# Schematic-1.net
KiCad netlist of a schematic drawn in EAGLE
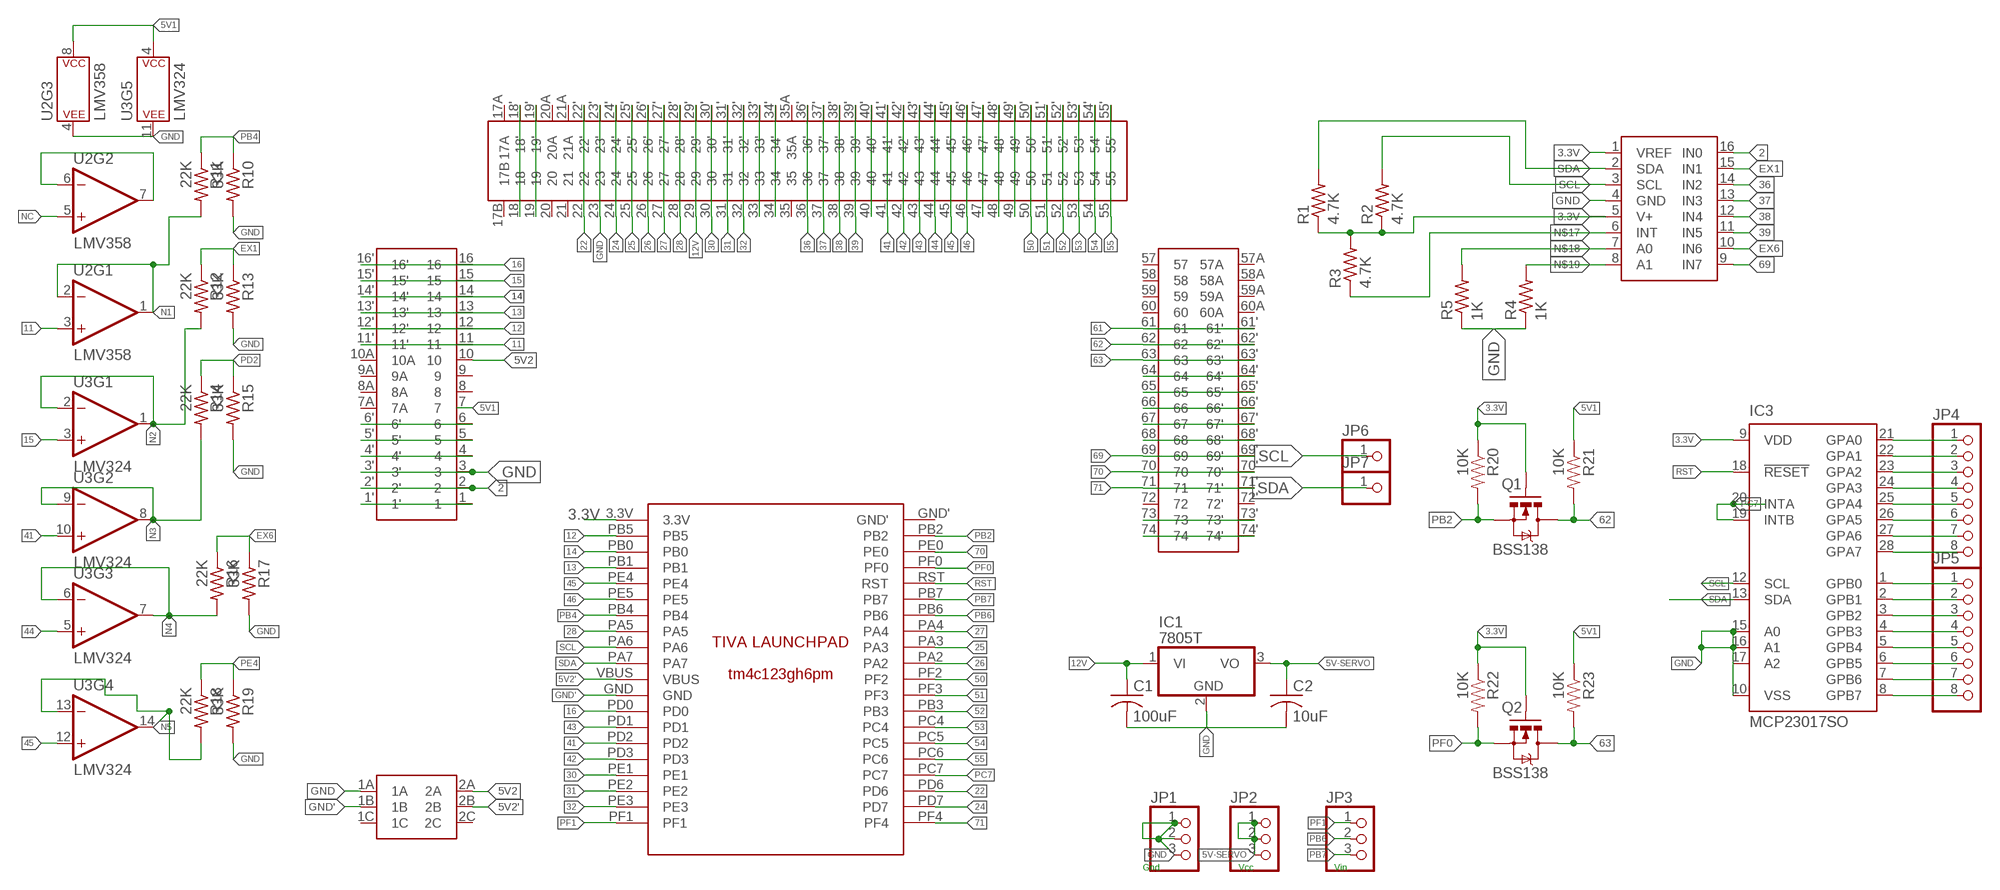
[diagram p0: schematic, sheet 1]

(export (version "E")
  (design (tool "Eeschema 10.0.6"))
  (components
    (comp (ref "C1")
      (value "100uF")
      (footprint "eagle-import:C025-030X050")
      (libsource (lib "eagle-import") (part "C-US025-030X050"))
    )
    (comp (ref "C2")
      (value "10uF")
      (footprint "eagle-import:C025-030X050")
      (libsource (lib "eagle-import") (part "C-US025-030X050"))
    )
    (comp (ref "IC1")
      (value "7805T")
      (footprint "eagle-import:TO220H")
      (libsource (lib "eagle-import") (part "78T05"))
    )
    (comp (ref "IC3")
      (value "MCP23017SO")
      (footprint "eagle-import:SO28W")
      (libsource (lib "eagle-import") (part "MCP23017SO"))
    )
    (comp (ref "JP1")
      (value "PINHD-1X3")
      (footprint "eagle-import:1X03")
      (libsource (lib "eagle-import") (part "PINHD-1X3"))
    )
    (comp (ref "JP2")
      (value "PINHD-1X3")
      (footprint "eagle-import:1X03")
      (libsource (lib "eagle-import") (part "PINHD-1X3"))
    )
    (comp (ref "JP3")
      (value "PINHD-1X3")
      (footprint "eagle-import:1X03")
      (libsource (lib "eagle-import") (part "PINHD-1X3"))
    )
    (comp (ref "JP4")
      (value "PINHD-1X8BIG")
      (footprint "eagle-import:1X08-BIG")
      (libsource (lib "eagle-import") (part "PINHD-1X8BIG"))
    )
    (comp (ref "JP5")
      (value "PINHD-1X8BIG")
      (footprint "eagle-import:1X08-BIG")
      (libsource (lib "eagle-import") (part "PINHD-1X8BIG"))
    )
    (comp (ref "JP6")
      (value "PINHD-1X1")
      (footprint "eagle-import:1X01")
      (libsource (lib "eagle-import") (part "PINHD-1X1"))
    )
    (comp (ref "JP7")
      (value "PINHD-1X1")
      (footprint "eagle-import:1X01")
      (libsource (lib "eagle-import") (part "PINHD-1X1"))
    )
    (comp (ref "Q1")
      (value "BSS138")
      (footprint "eagle-import:SOT23-3")
      (libsource (lib "eagle-import") (part "MOSFET-NCHANNELSMD"))
    )
    (comp (ref "Q2")
      (value "BSS138")
      (footprint "eagle-import:SOT23-3")
      (libsource (lib "eagle-import") (part "MOSFET-NCHANNELSMD"))
    )
    (comp (ref "R1")
      (value "4.7K")
      (footprint "eagle-import:M1206")
      (libsource (lib "eagle-import") (part "rcl_R-US_M1206"))
    )
    (comp (ref "R2")
      (value "4.7K")
      (footprint "eagle-import:M1206")
      (libsource (lib "eagle-import") (part "rcl_R-US_M1206"))
    )
    (comp (ref "R3")
      (value "4.7K")
      (footprint "eagle-import:M1206")
      (libsource (lib "eagle-import") (part "rcl_R-US_M1206"))
    )
    (comp (ref "R4")
      (value "1K")
      (footprint "eagle-import:M1206")
      (libsource (lib "eagle-import") (part "rcl_R-US_M1206"))
    )
    (comp (ref "R5")
      (value "1K")
      (footprint "eagle-import:M1206")
      (libsource (lib "eagle-import") (part "rcl_R-US_M1206"))
    )
    (comp (ref "R10")
      (value "33K")
      (footprint "eagle-import:M1206")
      (libsource (lib "eagle-import") (part "R-US_M1206"))
    )
    (comp (ref "R11")
      (value "22K")
      (footprint "eagle-import:M1206")
      (libsource (lib "eagle-import") (part "R-US_M1206"))
    )
    (comp (ref "R12")
      (value "22K")
      (footprint "eagle-import:M1206")
      (libsource (lib "eagle-import") (part "R-US_M1206"))
    )
    (comp (ref "R13")
      (value "33K")
      (footprint "eagle-import:M1206")
      (libsource (lib "eagle-import") (part "R-US_M1206"))
    )
    (comp (ref "R14")
      (value "22K")
      (footprint "eagle-import:M1206")
      (libsource (lib "eagle-import") (part "R-US_M1206"))
    )
    (comp (ref "R15")
      (value "33K")
      (footprint "eagle-import:M1206")
      (libsource (lib "eagle-import") (part "R-US_M1206"))
    )
    (comp (ref "R16")
      (value "22K")
      (footprint "eagle-import:M1206")
      (libsource (lib "eagle-import") (part "R-US_M1206"))
    )
    (comp (ref "R17")
      (value "33K")
      (footprint "eagle-import:M1206")
      (libsource (lib "eagle-import") (part "R-US_M1206"))
    )
    (comp (ref "R18")
      (value "22K")
      (footprint "eagle-import:M1206")
      (libsource (lib "eagle-import") (part "R-US_M1206"))
    )
    (comp (ref "R19")
      (value "33K")
      (footprint "eagle-import:M1206")
      (libsource (lib "eagle-import") (part "R-US_M1206"))
    )
    (comp (ref "R20")
      (value "10K")
      (footprint "eagle-import:1206")
      (libsource (lib "eagle-import") (part "RESISTOR1206"))
    )
    (comp (ref "R21")
      (value "10K")
      (footprint "eagle-import:1206")
      (libsource (lib "eagle-import") (part "RESISTOR1206"))
    )
    (comp (ref "R22")
      (value "10K")
      (footprint "eagle-import:1206")
      (libsource (lib "eagle-import") (part "RESISTOR1206"))
    )
    (comp (ref "R23")
      (value "10K")
      (footprint "eagle-import:1206")
      (libsource (lib "eagle-import") (part "RESISTOR1206"))
    )
    (comp (ref "U$1")
      (value "DAUGHTERBOARDDAUGHTERBOARD")
      (footprint "eagle-import:DAUGHTERBOARD")
      (libsource (lib "eagle-import") (part "DAUGHTERBOARDDAUGHTERBOARD"))
    )
    (comp (ref "U$2")
      (value "TIVA_LAUNCHPADTIVA_LAUNCHPAD")
      (footprint "eagle-import:TIVA_LAUNCHPAD")
      (libsource (lib "eagle-import") (part "TIVA_LAUNCHPADTIVA_LAUNCHPAD"))
    )
    (comp (ref "U$3")
      (value "SELF-LOCKING_SWITCHSELF-LOCKING_SWITCH")
      (footprint "eagle-import:SELF-LOCKING_SWITCH")
      (libsource (lib "eagle-import") (part "SELF-LOCKING_SWITCHSELF-LOCKING_SWITCH"))
    )
    (comp (ref "U$4")
      (value "ADC128D818")
      (footprint "eagle-import:ADC12_SD")
      (libsource (lib "eagle-import") (part "ADC128D818"))
    )
    (comp (ref "U2")
      (value "LMV358")
      (footprint "eagle-import:SO08")
      (libsource (lib "eagle-import") (part "LMV358SOIC"))
    )
    (comp (ref "U3")
      (value "LMV324")
      (footprint "eagle-import:SO14")
      (libsource (lib "eagle-import") (part "LMV324"))
    )
  )
  (nets
    (net (code "1") (name "2") (class "Default")
      (node (ref "U$1") (pin "2") (pinfunction "2_2") (pintype "output"))
      (node (ref "U$1") (pin "2'") (pinfunction "2'_2'") (pintype "output"))
      (node (ref "U$4") (pin "16") (pinfunction "IN0_16") (pintype "bidirectional"))
    )
    (net (code "2") (name "3.3V") (class "Default")
      (node (ref "IC3") (pin "9") (pinfunction "VDD_9") (pintype "power_in"))
      (node (ref "Q1") (pin "1") (pinfunction "G_1") (pintype "passive"))
      (node (ref "Q2") (pin "1") (pinfunction "G_1") (pintype "passive"))
      (node (ref "R1") (pin "1") (pinfunction "1_1") (pintype "passive"))
      (node (ref "R2") (pin "1") (pinfunction "1_1") (pintype "passive"))
      (node (ref "R20") (pin "1") (pinfunction "1_1") (pintype "passive"))
      (node (ref "R22") (pin "1") (pinfunction "1_1") (pintype "passive"))
      (node (ref "R3") (pin "2") (pinfunction "2_2") (pintype "passive"))
      (node (ref "U$2") (pin "3.3V") (pinfunction "3.3V_3.3V") (pintype "bidirectional"))
      (node (ref "U$4") (pin "1") (pinfunction "VREF_1") (pintype "bidirectional"))
      (node (ref "U$4") (pin "5") (pinfunction "V+_5") (pintype "bidirectional"))
    )
    (net (code "3") (name "5V-SERVO") (class "Default")
      (node (ref "C2") (pin "1") (pinfunction "1_1") (pintype "passive"))
      (node (ref "IC1") (pin "3") (pinfunction "VO_3") (pintype "passive"))
      (node (ref "JP2") (pin "1") (pinfunction "1_1") (pintype "passive"))
      (node (ref "JP2") (pin "2") (pinfunction "2_2") (pintype "passive"))
      (node (ref "JP2") (pin "3") (pinfunction "3_3") (pintype "passive"))
    )
    (net (code "4") (name "5V1") (class "Default")
      (node (ref "R21") (pin "1") (pinfunction "1_1") (pintype "passive"))
      (node (ref "R23") (pin "1") (pinfunction "1_1") (pintype "passive"))
      (node (ref "U$1") (pin "7") (pinfunction "7_7") (pintype "output"))
      (node (ref "U2") (pin "8") (pinfunction "P$V+_8") (pintype "bidirectional"))
      (node (ref "U3") (pin "4") (pinfunction "P$V+_4") (pintype "bidirectional"))
    )
    (net (code "5") (name "5V2") (class "Default")
      (node (ref "U$1") (pin "10") (pinfunction "10_10") (pintype "output"))
      (node (ref "U$3") (pin "2A") (pinfunction "2A_2A") (pintype "bidirectional"))
    )
    (net (code "6") (name "5V2'") (class "Default")
      (node (ref "U$2") (pin "VBUS") (pinfunction "VBUS_VBUS") (pintype "bidirectional"))
      (node (ref "U$3") (pin "2B") (pinfunction "2B_2B") (pintype "bidirectional"))
    )
    (net (code "7") (name "11") (class "Default")
      (node (ref "U$1") (pin "11") (pinfunction "11_11") (pintype "output"))
      (node (ref "U$1") (pin "11'") (pinfunction "11'_11'") (pintype "output"))
      (node (ref "U2") (pin "3") (pinfunction "+IN_3") (pintype "input"))
    )
    (net (code "8") (name "12") (class "Default")
      (node (ref "U$1") (pin "12") (pinfunction "12_12") (pintype "output"))
      (node (ref "U$1") (pin "12'") (pinfunction "12'_12'") (pintype "output"))
      (node (ref "U$2") (pin "PB5") (pinfunction "PB5_PB5") (pintype "bidirectional"))
    )
    (net (code "9") (name "12V") (class "Default")
      (node (ref "C1") (pin "1") (pinfunction "1_1") (pintype "passive"))
      (node (ref "IC1") (pin "1") (pinfunction "VI_1") (pintype "input"))
      (node (ref "U$1") (pin "29") (pinfunction "29_29") (pintype "output"))
      (node (ref "U$1") (pin "29'") (pinfunction "29'_29'") (pintype "output"))
    )
    (net (code "10") (name "13") (class "Default")
      (node (ref "U$1") (pin "13") (pinfunction "13_13") (pintype "output"))
      (node (ref "U$1") (pin "13'") (pinfunction "13'_13'") (pintype "output"))
      (node (ref "U$2") (pin "PB1") (pinfunction "PB1_PB1") (pintype "bidirectional"))
    )
    (net (code "11") (name "14") (class "Default")
      (node (ref "U$1") (pin "14") (pinfunction "14_14") (pintype "output"))
      (node (ref "U$1") (pin "14'") (pinfunction "14'_14'") (pintype "output"))
      (node (ref "U$2") (pin "PB0") (pinfunction "PB0_PB0") (pintype "bidirectional"))
    )
    (net (code "12") (name "15") (class "Default")
      (node (ref "U$1") (pin "15") (pinfunction "15_15") (pintype "output"))
      (node (ref "U$1") (pin "15'") (pinfunction "15'_15'") (pintype "output"))
      (node (ref "U3") (pin "3") (pinfunction "+IN_3") (pintype "input"))
    )
    (net (code "13") (name "16") (class "Default")
      (node (ref "U$1") (pin "16") (pinfunction "16_16") (pintype "output"))
      (node (ref "U$1") (pin "16'") (pinfunction "16'_16'") (pintype "output"))
      (node (ref "U$2") (pin "PD0") (pinfunction "PD0_PD0") (pintype "bidirectional"))
    )
    (net (code "14") (name "22") (class "Default")
      (node (ref "U$1") (pin "22") (pinfunction "22_22") (pintype "output"))
      (node (ref "U$1") (pin "22'") (pinfunction "22'_22'") (pintype "output"))
      (node (ref "U$2") (pin "PD6") (pinfunction "PD6_PD6") (pintype "bidirectional"))
    )
    (net (code "15") (name "24") (class "Default")
      (node (ref "U$1") (pin "24") (pinfunction "24_24") (pintype "output"))
      (node (ref "U$1") (pin "24'") (pinfunction "24'_24'") (pintype "output"))
      (node (ref "U$2") (pin "PD7") (pinfunction "PD7_PD7") (pintype "bidirectional"))
    )
    (net (code "16") (name "25") (class "Default")
      (node (ref "U$1") (pin "25") (pinfunction "25_25") (pintype "output"))
      (node (ref "U$1") (pin "25'") (pinfunction "25'_25'") (pintype "output"))
      (node (ref "U$2") (pin "PA3") (pinfunction "PA3_PA3") (pintype "bidirectional"))
    )
    (net (code "17") (name "26") (class "Default")
      (node (ref "U$1") (pin "26") (pinfunction "26_26") (pintype "output"))
      (node (ref "U$1") (pin "26'") (pinfunction "26'_26'") (pintype "output"))
      (node (ref "U$2") (pin "PA2") (pinfunction "PA2_PA2") (pintype "bidirectional"))
    )
    (net (code "18") (name "27") (class "Default")
      (node (ref "U$1") (pin "27") (pinfunction "27_27") (pintype "output"))
      (node (ref "U$1") (pin "27'") (pinfunction "27'_27'") (pintype "output"))
      (node (ref "U$2") (pin "PA4") (pinfunction "PA4_PA4") (pintype "bidirectional"))
    )
    (net (code "19") (name "28") (class "Default")
      (node (ref "U$1") (pin "28") (pinfunction "28_28") (pintype "output"))
      (node (ref "U$1") (pin "28'") (pinfunction "28'_28'") (pintype "output"))
      (node (ref "U$2") (pin "PA5") (pinfunction "PA5_PA5") (pintype "bidirectional"))
    )
    (net (code "20") (name "30") (class "Default")
      (node (ref "U$1") (pin "30") (pinfunction "30_30") (pintype "output"))
      (node (ref "U$1") (pin "30'") (pinfunction "30'_30'") (pintype "output"))
      (node (ref "U$2") (pin "PE1") (pinfunction "PE1_PE1") (pintype "bidirectional"))
    )
    (net (code "21") (name "31") (class "Default")
      (node (ref "U$1") (pin "31") (pinfunction "31_31") (pintype "output"))
      (node (ref "U$1") (pin "31'") (pinfunction "31'_31'") (pintype "output"))
      (node (ref "U$2") (pin "PE2") (pinfunction "PE2_PE2") (pintype "bidirectional"))
    )
    (net (code "22") (name "32") (class "Default")
      (node (ref "U$1") (pin "32") (pinfunction "32_32") (pintype "output"))
      (node (ref "U$1") (pin "32'") (pinfunction "32'_32'") (pintype "output"))
      (node (ref "U$2") (pin "PE3") (pinfunction "PE3_PE3") (pintype "bidirectional"))
    )
    (net (code "23") (name "36") (class "Default")
      (node (ref "U$1") (pin "36") (pinfunction "36_36") (pintype "output"))
      (node (ref "U$1") (pin "36'") (pinfunction "36'_36'") (pintype "output"))
      (node (ref "U$4") (pin "14") (pinfunction "IN2_14") (pintype "bidirectional"))
    )
    (net (code "24") (name "37") (class "Default")
      (node (ref "U$1") (pin "37") (pinfunction "37_37") (pintype "output"))
      (node (ref "U$1") (pin "37'") (pinfunction "37'_37'") (pintype "output"))
      (node (ref "U$4") (pin "13") (pinfunction "IN3_13") (pintype "bidirectional"))
    )
    (net (code "25") (name "38") (class "Default")
      (node (ref "U$1") (pin "38") (pinfunction "38_38") (pintype "output"))
      (node (ref "U$1") (pin "38'") (pinfunction "38'_38'") (pintype "output"))
      (node (ref "U$4") (pin "12") (pinfunction "IN4_12") (pintype "bidirectional"))
    )
    (net (code "26") (name "39") (class "Default")
      (node (ref "U$1") (pin "39") (pinfunction "39_39") (pintype "output"))
      (node (ref "U$1") (pin "39'") (pinfunction "39'_39'") (pintype "output"))
      (node (ref "U$4") (pin "11") (pinfunction "IN5_11") (pintype "bidirectional"))
    )
    (net (code "27") (name "41") (class "Default")
      (node (ref "U$1") (pin "41") (pinfunction "41_41") (pintype "output"))
      (node (ref "U$1") (pin "41'") (pinfunction "41'_41'") (pintype "output"))
      (node (ref "U$2") (pin "PD2") (pinfunction "PD2_PD2") (pintype "bidirectional"))
      (node (ref "U3") (pin "10") (pinfunction "+IN_10") (pintype "input"))
    )
    (net (code "28") (name "42") (class "Default")
      (node (ref "U$1") (pin "42") (pinfunction "42_42") (pintype "output"))
      (node (ref "U$1") (pin "42'") (pinfunction "42'_42'") (pintype "output"))
      (node (ref "U$2") (pin "PD3") (pinfunction "PD3_PD3") (pintype "bidirectional"))
    )
    (net (code "29") (name "43") (class "Default")
      (node (ref "U$1") (pin "43") (pinfunction "43_43") (pintype "output"))
      (node (ref "U$1") (pin "43'") (pinfunction "43'_43'") (pintype "output"))
      (node (ref "U$2") (pin "PD1") (pinfunction "PD1_PD1") (pintype "bidirectional"))
    )
    (net (code "30") (name "44") (class "Default")
      (node (ref "U$1") (pin "44") (pinfunction "44_44") (pintype "output"))
      (node (ref "U$1") (pin "44'") (pinfunction "44'_44'") (pintype "output"))
      (node (ref "U3") (pin "5") (pinfunction "+IN_5") (pintype "input"))
    )
    (net (code "31") (name "45") (class "Default")
      (node (ref "U$1") (pin "45") (pinfunction "45_45") (pintype "output"))
      (node (ref "U$1") (pin "45'") (pinfunction "45'_45'") (pintype "output"))
      (node (ref "U$2") (pin "PE4") (pinfunction "PE4_PE4") (pintype "bidirectional"))
      (node (ref "U3") (pin "12") (pinfunction "+IN_12") (pintype "input"))
    )
    (net (code "32") (name "46") (class "Default")
      (node (ref "U$1") (pin "46") (pinfunction "46_46") (pintype "output"))
      (node (ref "U$1") (pin "46'") (pinfunction "46'_46'") (pintype "output"))
      (node (ref "U$2") (pin "PE5") (pinfunction "PE5_PE5") (pintype "bidirectional"))
    )
    (net (code "33") (name "50") (class "Default")
      (node (ref "U$1") (pin "50") (pinfunction "50_50") (pintype "output"))
      (node (ref "U$1") (pin "50'") (pinfunction "50'_50'") (pintype "output"))
      (node (ref "U$2") (pin "PF2") (pinfunction "PF2_PF2") (pintype "bidirectional"))
    )
    (net (code "34") (name "51") (class "Default")
      (node (ref "U$1") (pin "51") (pinfunction "51_51") (pintype "output"))
      (node (ref "U$1") (pin "51'") (pinfunction "51'_51'") (pintype "output"))
      (node (ref "U$2") (pin "PF3") (pinfunction "PF3_PF3") (pintype "bidirectional"))
    )
    (net (code "35") (name "52") (class "Default")
      (node (ref "U$1") (pin "52") (pinfunction "52_52") (pintype "output"))
      (node (ref "U$1") (pin "52'") (pinfunction "52'_52'") (pintype "output"))
      (node (ref "U$2") (pin "PB3") (pinfunction "PB3_PB3") (pintype "bidirectional"))
    )
    (net (code "36") (name "53") (class "Default")
      (node (ref "U$1") (pin "53") (pinfunction "53_53") (pintype "output"))
      (node (ref "U$1") (pin "53'") (pinfunction "53'_53'") (pintype "output"))
      (node (ref "U$2") (pin "PC4") (pinfunction "PC4_PC4") (pintype "bidirectional"))
    )
    (net (code "37") (name "54") (class "Default")
      (node (ref "U$1") (pin "54") (pinfunction "54_54") (pintype "output"))
      (node (ref "U$1") (pin "54'") (pinfunction "54'_54'") (pintype "output"))
      (node (ref "U$2") (pin "PC5") (pinfunction "PC5_PC5") (pintype "bidirectional"))
    )
    (net (code "38") (name "55") (class "Default")
      (node (ref "U$1") (pin "55") (pinfunction "55_55") (pintype "output"))
      (node (ref "U$1") (pin "55'") (pinfunction "55'_55'") (pintype "output"))
      (node (ref "U$2") (pin "PC6") (pinfunction "PC6_PC6") (pintype "bidirectional"))
    )
    (net (code "39") (name "61") (class "Default")
      (node (ref "U$1") (pin "61") (pinfunction "61_61") (pintype "output"))
      (node (ref "U$1") (pin "61'") (pinfunction "61'_61'") (pintype "output"))
    )
    (net (code "40") (name "62") (class "Default")
      (node (ref "Q1") (pin "3") (pinfunction "D_3") (pintype "passive"))
      (node (ref "R21") (pin "2") (pinfunction "2_2") (pintype "passive"))
      (node (ref "U$1") (pin "62") (pinfunction "62_62") (pintype "output"))
      (node (ref "U$1") (pin "62'") (pinfunction "62'_62'") (pintype "output"))
    )
    (net (code "41") (name "63") (class "Default")
      (node (ref "Q2") (pin "3") (pinfunction "D_3") (pintype "passive"))
      (node (ref "R23") (pin "2") (pinfunction "2_2") (pintype "passive"))
      (node (ref "U$1") (pin "63") (pinfunction "63_63") (pintype "output"))
      (node (ref "U$1") (pin "63'") (pinfunction "63'_63'") (pintype "output"))
    )
    (net (code "42") (name "69") (class "Default")
      (node (ref "U$1") (pin "69") (pinfunction "69_69") (pintype "output"))
      (node (ref "U$1") (pin "69'") (pinfunction "69'_69'") (pintype "output"))
      (node (ref "U$4") (pin "9") (pinfunction "IN7_9") (pintype "bidirectional"))
    )
    (net (code "43") (name "70") (class "Default")
      (node (ref "U$1") (pin "70") (pinfunction "70_70") (pintype "output"))
      (node (ref "U$1") (pin "70'") (pinfunction "70'_70'") (pintype "output"))
      (node (ref "U$2") (pin "PE0") (pinfunction "PE0_PE0") (pintype "bidirectional"))
    )
    (net (code "44") (name "71") (class "Default")
      (node (ref "U$1") (pin "71") (pinfunction "71_71") (pintype "output"))
      (node (ref "U$1") (pin "71'") (pinfunction "71'_71'") (pintype "output"))
      (node (ref "U$2") (pin "PF4") (pinfunction "PF4_PF4") (pintype "bidirectional"))
    )
    (net (code "45") (name "EX1") (class "Default")
      (node (ref "R12") (pin "1") (pinfunction "1_1") (pintype "passive"))
      (node (ref "R13") (pin "1") (pinfunction "1_1") (pintype "passive"))
      (node (ref "U$4") (pin "15") (pinfunction "IN1_15") (pintype "bidirectional"))
    )
    (net (code "46") (name "EX6") (class "Default")
      (node (ref "R16") (pin "1") (pinfunction "1_1") (pintype "passive"))
      (node (ref "R17") (pin "1") (pinfunction "1_1") (pintype "passive"))
      (node (ref "U$4") (pin "10") (pinfunction "IN6_10") (pintype "bidirectional"))
    )
    (net (code "47") (name "GND") (class "Default")
      (node (ref "C1") (pin "2") (pinfunction "2_2") (pintype "passive"))
      (node (ref "C2") (pin "2") (pinfunction "2_2") (pintype "passive"))
      (node (ref "IC1") (pin "2") (pinfunction "GND_2") (pintype "passive"))
      (node (ref "IC3") (pin "10") (pinfunction "VSS_10") (pintype "power_in"))
      (node (ref "IC3") (pin "15") (pinfunction "A0_15") (pintype "input"))
      (node (ref "IC3") (pin "16") (pinfunction "A1_16") (pintype "input"))
      (node (ref "IC3") (pin "17") (pinfunction "A2_17") (pintype "input"))
      (node (ref "JP1") (pin "1") (pinfunction "1_1") (pintype "passive"))
      (node (ref "JP1") (pin "2") (pinfunction "2_2") (pintype "passive"))
      (node (ref "JP1") (pin "3") (pinfunction "3_3") (pintype "passive"))
      (node (ref "R10") (pin "2") (pinfunction "2_2") (pintype "passive"))
      (node (ref "R13") (pin "2") (pinfunction "2_2") (pintype "passive"))
      (node (ref "R15") (pin "2") (pinfunction "2_2") (pintype "passive"))
      (node (ref "R17") (pin "2") (pinfunction "2_2") (pintype "passive"))
      (node (ref "R19") (pin "2") (pinfunction "2_2") (pintype "passive"))
      (node (ref "R4") (pin "1") (pinfunction "1_1") (pintype "passive"))
      (node (ref "R5") (pin "1") (pinfunction "1_1") (pintype "passive"))
      (node (ref "U$1") (pin "23") (pinfunction "23_23") (pintype "output"))
      (node (ref "U$1") (pin "23'") (pinfunction "23'_23'") (pintype "output"))
      (node (ref "U$1") (pin "3") (pinfunction "3_3") (pintype "output"))
      (node (ref "U$1") (pin "3'") (pinfunction "3'_3'") (pintype "output"))
      (node (ref "U$3") (pin "1A") (pinfunction "1A_1A") (pintype "bidirectional"))
      (node (ref "U$4") (pin "4") (pinfunction "GND_4") (pintype "bidirectional"))
      (node (ref "U2") (pin "4") (pinfunction "P$V-_4") (pintype "bidirectional"))
      (node (ref "U3") (pin "11") (pinfunction "P$V-_11") (pintype "bidirectional"))
    )
    (net (code "48") (name "GND'") (class "Default")
      (node (ref "U$2") (pin "GND") (pinfunction "GND_GND") (pintype "bidirectional"))
      (node (ref "U$3") (pin "1B") (pinfunction "1B_1B") (pintype "bidirectional"))
    )
    (net (code "49") (name "N$17") (class "Default")
      (node (ref "R3") (pin "1") (pinfunction "1_1") (pintype "passive"))
      (node (ref "U$4") (pin "6") (pinfunction "INT_6") (pintype "bidirectional"))
    )
    (net (code "50") (name "N$18") (class "Default")
      (node (ref "R5") (pin "2") (pinfunction "2_2") (pintype "passive"))
      (node (ref "U$4") (pin "7") (pinfunction "A0_7") (pintype "bidirectional"))
    )
    (net (code "51") (name "N$19") (class "Default")
      (node (ref "R4") (pin "2") (pinfunction "2_2") (pintype "passive"))
      (node (ref "U$4") (pin "8") (pinfunction "A1_8") (pintype "bidirectional"))
    )
    (net (code "52") (name "N1") (class "Default")
      (node (ref "R11") (pin "2") (pinfunction "2_2") (pintype "passive"))
      (node (ref "U2") (pin "1") (pinfunction "OUT_1") (pintype "output"))
      (node (ref "U2") (pin "2") (pinfunction "-IN_2") (pintype "input"))
    )
    (net (code "53") (name "N2") (class "Default")
      (node (ref "R12") (pin "2") (pinfunction "2_2") (pintype "passive"))
      (node (ref "U3") (pin "1") (pinfunction "OUT_1") (pintype "output"))
      (node (ref "U3") (pin "2") (pinfunction "-IN_2") (pintype "input"))
    )
    (net (code "54") (name "N3") (class "Default")
      (node (ref "R14") (pin "2") (pinfunction "2_2") (pintype "passive"))
      (node (ref "U3") (pin "8") (pinfunction "OUT_8") (pintype "output"))
      (node (ref "U3") (pin "9") (pinfunction "-IN_9") (pintype "input"))
    )
    (net (code "55") (name "N4") (class "Default")
      (node (ref "R16") (pin "2") (pinfunction "2_2") (pintype "passive"))
      (node (ref "U3") (pin "6") (pinfunction "-IN_6") (pintype "input"))
      (node (ref "U3") (pin "7") (pinfunction "OUT_7") (pintype "output"))
    )
    (net (code "56") (name "N5") (class "Default")
      (node (ref "R18") (pin "2") (pinfunction "2_2") (pintype "passive"))
      (node (ref "U3") (pin "13") (pinfunction "-IN_13") (pintype "input"))
      (node (ref "U3") (pin "14") (pinfunction "OUT_14") (pintype "output"))
    )
    (net (code "57") (name "NC") (class "Default")
      (node (ref "U2") (pin "5") (pinfunction "+IN_5") (pintype "input"))
    )
    (net (code "58") (name "Net-(IC3-GPA0)") (class "Default")
      (node (ref "IC3") (pin "21") (pinfunction "GPA0_21") (pintype "bidirectional"))
      (node (ref "JP4") (pin "1") (pinfunction "1_1") (pintype "passive"))
    )
    (net (code "59") (name "Net-(IC3-GPA1)") (class "Default")
      (node (ref "IC3") (pin "22") (pinfunction "GPA1_22") (pintype "bidirectional"))
      (node (ref "JP4") (pin "2") (pinfunction "2_2") (pintype "passive"))
    )
    (net (code "60") (name "Net-(IC3-GPA2)") (class "Default")
      (node (ref "IC3") (pin "23") (pinfunction "GPA2_23") (pintype "bidirectional"))
      (node (ref "JP4") (pin "3") (pinfunction "3_3") (pintype "passive"))
    )
    (net (code "61") (name "Net-(IC3-GPA3)") (class "Default")
      (node (ref "IC3") (pin "24") (pinfunction "GPA3_24") (pintype "bidirectional"))
      (node (ref "JP4") (pin "4") (pinfunction "4_4") (pintype "passive"))
    )
    (net (code "62") (name "Net-(IC3-GPA4)") (class "Default")
      (node (ref "IC3") (pin "25") (pinfunction "GPA4_25") (pintype "bidirectional"))
      (node (ref "JP4") (pin "5") (pinfunction "5_5") (pintype "passive"))
    )
    (net (code "63") (name "Net-(IC3-GPA5)") (class "Default")
      (node (ref "IC3") (pin "26") (pinfunction "GPA5_26") (pintype "bidirectional"))
      (node (ref "JP4") (pin "6") (pinfunction "6_6") (pintype "passive"))
    )
    (net (code "64") (name "Net-(IC3-GPA6)") (class "Default")
      (node (ref "IC3") (pin "27") (pinfunction "GPA6_27") (pintype "bidirectional"))
      (node (ref "JP4") (pin "7") (pinfunction "7_7") (pintype "passive"))
    )
    (net (code "65") (name "Net-(IC3-GPA7)") (class "Default")
      (node (ref "IC3") (pin "28") (pinfunction "GPA7_28") (pintype "bidirectional"))
      (node (ref "JP4") (pin "8") (pinfunction "8_8") (pintype "passive"))
    )
    (net (code "66") (name "Net-(IC3-GPB0)") (class "Default")
      (node (ref "IC3") (pin "1") (pinfunction "GPB0_1") (pintype "bidirectional"))
      (node (ref "JP5") (pin "1") (pinfunction "1_1") (pintype "passive"))
    )
    (net (code "67") (name "Net-(IC3-GPB1)") (class "Default")
      (node (ref "IC3") (pin "2") (pinfunction "GPB1_2") (pintype "bidirectional"))
      (node (ref "JP5") (pin "2") (pinfunction "2_2") (pintype "passive"))
    )
    (net (code "68") (name "Net-(IC3-GPB2)") (class "Default")
      (node (ref "IC3") (pin "3") (pinfunction "GPB2_3") (pintype "bidirectional"))
      (node (ref "JP5") (pin "3") (pinfunction "3_3") (pintype "passive"))
    )
    (net (code "69") (name "Net-(IC3-GPB3)") (class "Default")
      (node (ref "IC3") (pin "4") (pinfunction "GPB3_4") (pintype "bidirectional"))
      (node (ref "JP5") (pin "4") (pinfunction "4_4") (pintype "passive"))
    )
    (net (code "70") (name "Net-(IC3-GPB4)") (class "Default")
      (node (ref "IC3") (pin "5") (pinfunction "GPB4_5") (pintype "bidirectional"))
      (node (ref "JP5") (pin "5") (pinfunction "5_5") (pintype "passive"))
    )
    (net (code "71") (name "Net-(IC3-GPB5)") (class "Default")
      (node (ref "IC3") (pin "6") (pinfunction "GPB5_6") (pintype "bidirectional"))
      (node (ref "JP5") (pin "6") (pinfunction "6_6") (pintype "passive"))
    )
    (net (code "72") (name "Net-(IC3-GPB6)") (class "Default")
      (node (ref "IC3") (pin "7") (pinfunction "GPB6_7") (pintype "bidirectional"))
      (node (ref "JP5") (pin "7") (pinfunction "7_7") (pintype "passive"))
    )
    (net (code "73") (name "Net-(IC3-GPB7)") (class "Default")
      (node (ref "IC3") (pin "8") (pinfunction "GPB7_8") (pintype "bidirectional"))
      (node (ref "JP5") (pin "8") (pinfunction "8_8") (pintype "passive"))
    )
    (net (code "74") (name "Net-(U$1-Pad1')") (class "Default")
      (node (ref "U$1") (pin "1") (pinfunction "1_1") (pintype "output"))
      (node (ref "U$1") (pin "1'") (pinfunction "1'_1'") (pintype "output"))
    )
    (net (code "75") (name "Net-(U$1-Pad4')") (class "Default")
      (node (ref "U$1") (pin "4") (pinfunction "4_4") (pintype "output"))
      (node (ref "U$1") (pin "4'") (pinfunction "4'_4'") (pintype "output"))
    )
    (net (code "76") (name "Net-(U$1-Pad5')") (class "Default")
      (node (ref "U$1") (pin "5") (pinfunction "5_5") (pintype "output"))
      (node (ref "U$1") (pin "5'") (pinfunction "5'_5'") (pintype "output"))
    )
    (net (code "77") (name "Net-(U$1-Pad6')") (class "Default")
      (node (ref "U$1") (pin "6") (pinfunction "6_6") (pintype "output"))
      (node (ref "U$1") (pin "6'") (pinfunction "6'_6'") (pintype "output"))
    )
    (net (code "78") (name "Net-(U$1-Pad18')") (class "Default")
      (node (ref "U$1") (pin "18") (pinfunction "18_18") (pintype "output"))
      (node (ref "U$1") (pin "18'") (pinfunction "18'_18'") (pintype "output"))
    )
    (net (code "79") (name "Net-(U$1-Pad19')") (class "Default")
      (node (ref "U$1") (pin "19") (pinfunction "19_19") (pintype "output"))
      (node (ref "U$1") (pin "19'") (pinfunction "19'_19'") (pintype "output"))
    )
    (net (code "80") (name "Net-(U$1-Pad33')") (class "Default")
      (node (ref "U$1") (pin "33") (pinfunction "33_33") (pintype "output"))
      (node (ref "U$1") (pin "33'") (pinfunction "33'_33'") (pintype "output"))
    )
    (net (code "81") (name "Net-(U$1-Pad34')") (class "Default")
      (node (ref "U$1") (pin "34") (pinfunction "34_34") (pintype "output"))
      (node (ref "U$1") (pin "34'") (pinfunction "34'_34'") (pintype "output"))
    )
    (net (code "82") (name "Net-(U$1-Pad40')") (class "Default")
      (node (ref "U$1") (pin "40") (pinfunction "40_40") (pintype "output"))
      (node (ref "U$1") (pin "40'") (pinfunction "40'_40'") (pintype "output"))
    )
    (net (code "83") (name "Net-(U$1-Pad47')") (class "Default")
      (node (ref "U$1") (pin "47") (pinfunction "47_47") (pintype "output"))
      (node (ref "U$1") (pin "47'") (pinfunction "47'_47'") (pintype "output"))
    )
    (net (code "84") (name "Net-(U$1-Pad48')") (class "Default")
      (node (ref "U$1") (pin "48") (pinfunction "48_48") (pintype "output"))
      (node (ref "U$1") (pin "48'") (pinfunction "48'_48'") (pintype "output"))
    )
    (net (code "85") (name "Net-(U$1-Pad49')") (class "Default")
      (node (ref "U$1") (pin "49") (pinfunction "49_49") (pintype "output"))
      (node (ref "U$1") (pin "49'") (pinfunction "49'_49'") (pintype "output"))
    )
    (net (code "86") (name "Net-(U$1-Pad64')") (class "Default")
      (node (ref "U$1") (pin "64") (pinfunction "64_64") (pintype "output"))
      (node (ref "U$1") (pin "64'") (pinfunction "64'_64'") (pintype "output"))
    )
    (net (code "87") (name "Net-(U$1-Pad65')") (class "Default")
      (node (ref "U$1") (pin "65") (pinfunction "65_65") (pintype "output"))
      (node (ref "U$1") (pin "65'") (pinfunction "65'_65'") (pintype "output"))
    )
    (net (code "88") (name "Net-(U$1-Pad66')") (class "Default")
      (node (ref "U$1") (pin "66") (pinfunction "66_66") (pintype "output"))
      (node (ref "U$1") (pin "66'") (pinfunction "66'_66'") (pintype "output"))
    )
    (net (code "89") (name "Net-(U$1-Pad67')") (class "Default")
      (node (ref "U$1") (pin "67") (pinfunction "67_67") (pintype "output"))
      (node (ref "U$1") (pin "67'") (pinfunction "67'_67'") (pintype "output"))
    )
    (net (code "90") (name "Net-(U$1-Pad68')") (class "Default")
      (node (ref "U$1") (pin "68") (pinfunction "68_68") (pintype "output"))
      (node (ref "U$1") (pin "68'") (pinfunction "68'_68'") (pintype "output"))
    )
    (net (code "91") (name "Net-(U$1-Pad73')") (class "Default")
      (node (ref "U$1") (pin "73") (pinfunction "73_73") (pintype "output"))
      (node (ref "U$1") (pin "73'") (pinfunction "73'_73'") (pintype "output"))
    )
    (net (code "92") (name "Net-(U$1-Pad74')") (class "Default")
      (node (ref "U$1") (pin "74") (pinfunction "74_74") (pintype "output"))
      (node (ref "U$1") (pin "74'") (pinfunction "74'_74'") (pintype "output"))
    )
    (net (code "93") (name "Net-(U2B--IN)") (class "Default")
      (node (ref "U2") (pin "6") (pinfunction "-IN_6") (pintype "input"))
      (node (ref "U2") (pin "7") (pinfunction "OUT_7") (pintype "output"))
    )
    (net (code "94") (name "PB2") (class "Default")
      (node (ref "Q1") (pin "2") (pinfunction "S_2") (pintype "passive"))
      (node (ref "R20") (pin "2") (pinfunction "2_2") (pintype "passive"))
      (node (ref "U$2") (pin "PB2") (pinfunction "PB2_PB2") (pintype "bidirectional"))
    )
    (net (code "95") (name "PB4") (class "Default")
      (node (ref "R10") (pin "1") (pinfunction "1_1") (pintype "passive"))
      (node (ref "R11") (pin "1") (pinfunction "1_1") (pintype "passive"))
      (node (ref "U$2") (pin "PB4") (pinfunction "PB4_PB4") (pintype "bidirectional"))
    )
    (net (code "96") (name "PB6") (class "Default")
      (node (ref "JP3") (pin "2") (pinfunction "2_2") (pintype "passive"))
      (node (ref "U$2") (pin "PB6") (pinfunction "PB6_PB6") (pintype "bidirectional"))
    )
    (net (code "97") (name "PB7") (class "Default")
      (node (ref "JP3") (pin "3") (pinfunction "3_3") (pintype "passive"))
      (node (ref "U$2") (pin "PB7") (pinfunction "PB7_PB7") (pintype "bidirectional"))
    )
    (net (code "98") (name "PC7") (class "Default")
      (node (ref "IC3") (pin "19") (pinfunction "INTB_19") (pintype "output"))
      (node (ref "IC3") (pin "20") (pinfunction "INTA_20") (pintype "output"))
      (node (ref "U$2") (pin "PC7") (pinfunction "PC7_PC7") (pintype "bidirectional"))
    )
    (net (code "99") (name "PD2") (class "Default")
      (node (ref "R14") (pin "1") (pinfunction "1_1") (pintype "passive"))
      (node (ref "R15") (pin "1") (pinfunction "1_1") (pintype "passive"))
    )
    (net (code "100") (name "PE4") (class "Default")
      (node (ref "R18") (pin "1") (pinfunction "1_1") (pintype "passive"))
      (node (ref "R19") (pin "1") (pinfunction "1_1") (pintype "passive"))
    )
    (net (code "101") (name "PF0") (class "Default")
      (node (ref "Q2") (pin "2") (pinfunction "S_2") (pintype "passive"))
      (node (ref "R22") (pin "2") (pinfunction "2_2") (pintype "passive"))
      (node (ref "U$2") (pin "PF0") (pinfunction "PF0_PF0") (pintype "bidirectional"))
    )
    (net (code "102") (name "PF1") (class "Default")
      (node (ref "JP3") (pin "1") (pinfunction "1_1") (pintype "passive"))
      (node (ref "U$2") (pin "PF1") (pinfunction "PF1_PF1") (pintype "bidirectional"))
    )
    (net (code "103") (name "RST") (class "Default")
      (node (ref "IC3") (pin "18") (pinfunction "~{RESET}_18") (pintype "input"))
      (node (ref "U$2") (pin "RST") (pinfunction "RST_RST") (pintype "bidirectional"))
    )
    (net (code "104") (name "SCL") (class "Default")
      (node (ref "IC3") (pin "12") (pinfunction "SCL_12") (pintype "input"))
      (node (ref "JP6") (pin "1") (pinfunction "1_1") (pintype "passive"))
      (node (ref "R2") (pin "2") (pinfunction "2_2") (pintype "passive"))
      (node (ref "U$2") (pin "PA6") (pinfunction "PA6_PA6") (pintype "bidirectional"))
      (node (ref "U$4") (pin "3") (pinfunction "SCL_3") (pintype "bidirectional"))
    )
    (net (code "105") (name "SDA") (class "Default")
      (node (ref "IC3") (pin "13") (pinfunction "SDA_13") (pintype "bidirectional"))
      (node (ref "JP7") (pin "1") (pinfunction "1_1") (pintype "passive"))
      (node (ref "R1") (pin "2") (pinfunction "2_2") (pintype "passive"))
      (node (ref "U$2") (pin "PA7") (pinfunction "PA7_PA7") (pintype "bidirectional"))
      (node (ref "U$4") (pin "2") (pinfunction "SDA_2") (pintype "bidirectional"))
    )
    (net (code "106") (name "unconnected-(U$1-Pad7A)") (class "Default")
      (node (ref "U$1") (pin "7A") (pinfunction "7A_7A") (pintype "output"))
    )
    (net (code "107") (name "unconnected-(U$1-Pad8)") (class "Default")
      (node (ref "U$1") (pin "8") (pinfunction "8_8") (pintype "output"))
    )
    (net (code "108") (name "unconnected-(U$1-Pad8A)") (class "Default")
      (node (ref "U$1") (pin "8A") (pinfunction "8A_8A") (pintype "output"))
    )
    (net (code "109") (name "unconnected-(U$1-Pad9)") (class "Default")
      (node (ref "U$1") (pin "9") (pinfunction "9_9") (pintype "output"))
    )
    (net (code "110") (name "unconnected-(U$1-Pad9A)") (class "Default")
      (node (ref "U$1") (pin "9A") (pinfunction "9A_9A") (pintype "output"))
    )
    (net (code "111") (name "unconnected-(U$1-Pad10A)") (class "Default")
      (node (ref "U$1") (pin "10A") (pinfunction "10A_10A") (pintype "output"))
    )
    (net (code "112") (name "unconnected-(U$1-Pad17A)") (class "Default")
      (node (ref "U$1") (pin "17A") (pinfunction "17A_17A") (pintype "output"))
    )
    (net (code "113") (name "unconnected-(U$1-Pad17B)") (class "Default")
      (node (ref "U$1") (pin "17B") (pinfunction "17B_17B") (pintype "output"))
    )
    (net (code "114") (name "unconnected-(U$1-Pad20)") (class "Default")
      (node (ref "U$1") (pin "20") (pinfunction "20_20") (pintype "output"))
    )
    (net (code "115") (name "unconnected-(U$1-Pad20A)") (class "Default")
      (node (ref "U$1") (pin "20A") (pinfunction "20A_20A") (pintype "output"))
    )
    (net (code "116") (name "unconnected-(U$1-Pad21)") (class "Default")
      (node (ref "U$1") (pin "21") (pinfunction "21_21") (pintype "output"))
    )
    (net (code "117") (name "unconnected-(U$1-Pad21A)") (class "Default")
      (node (ref "U$1") (pin "21A") (pinfunction "21A_21A") (pintype "output"))
    )
    (net (code "118") (name "unconnected-(U$1-Pad35)") (class "Default")
      (node (ref "U$1") (pin "35") (pinfunction "35_35") (pintype "output"))
    )
    (net (code "119") (name "unconnected-(U$1-Pad35A)") (class "Default")
      (node (ref "U$1") (pin "35A") (pinfunction "35A_35A") (pintype "output"))
    )
    (net (code "120") (name "unconnected-(U$1-Pad57)") (class "Default")
      (node (ref "U$1") (pin "57") (pinfunction "57_57") (pintype "output"))
    )
    (net (code "121") (name "unconnected-(U$1-Pad57A)") (class "Default")
      (node (ref "U$1") (pin "57A") (pinfunction "57A_57A") (pintype "output"))
    )
    (net (code "122") (name "unconnected-(U$1-Pad58)") (class "Default")
      (node (ref "U$1") (pin "58") (pinfunction "58_58") (pintype "output"))
    )
    (net (code "123") (name "unconnected-(U$1-Pad58A)") (class "Default")
      (node (ref "U$1") (pin "58A") (pinfunction "58A_58A") (pintype "output"))
    )
    (net (code "124") (name "unconnected-(U$1-Pad59)") (class "Default")
      (node (ref "U$1") (pin "59") (pinfunction "59_59") (pintype "output"))
    )
    (net (code "125") (name "unconnected-(U$1-Pad59A)") (class "Default")
      (node (ref "U$1") (pin "59A") (pinfunction "59A_59A") (pintype "output"))
    )
    (net (code "126") (name "unconnected-(U$1-Pad60)") (class "Default")
      (node (ref "U$1") (pin "60") (pinfunction "60_60") (pintype "output"))
    )
    (net (code "127") (name "unconnected-(U$1-Pad60A)") (class "Default")
      (node (ref "U$1") (pin "60A") (pinfunction "60A_60A") (pintype "output"))
    )
    (net (code "128") (name "unconnected-(U$1-Pad72')") (class "Default")
      (node (ref "U$1") (pin "72'") (pinfunction "72'_72'") (pintype "output"))
    )
    (net (code "129") (name "unconnected-(U$1-Pad72)") (class "Default")
      (node (ref "U$1") (pin "72") (pinfunction "72_72") (pintype "output"))
    )
    (net (code "130") (name "unconnected-(U$2-PadGND')") (class "Default")
      (node (ref "U$2") (pin "GND'") (pinfunction "GND'_GND'") (pintype "bidirectional"))
    )
    (net (code "131") (name "unconnected-(U$3-Pad1C)") (class "Default")
      (node (ref "U$3") (pin "1C") (pinfunction "1C_1C") (pintype "bidirectional"))
    )
    (net (code "132") (name "unconnected-(U$3-Pad2C)") (class "Default")
      (node (ref "U$3") (pin "2C") (pinfunction "2C_2C") (pintype "bidirectional"))
    )
  )
)
